# untitled.net
KiCad netlist of a schematic drawn in EAGLE
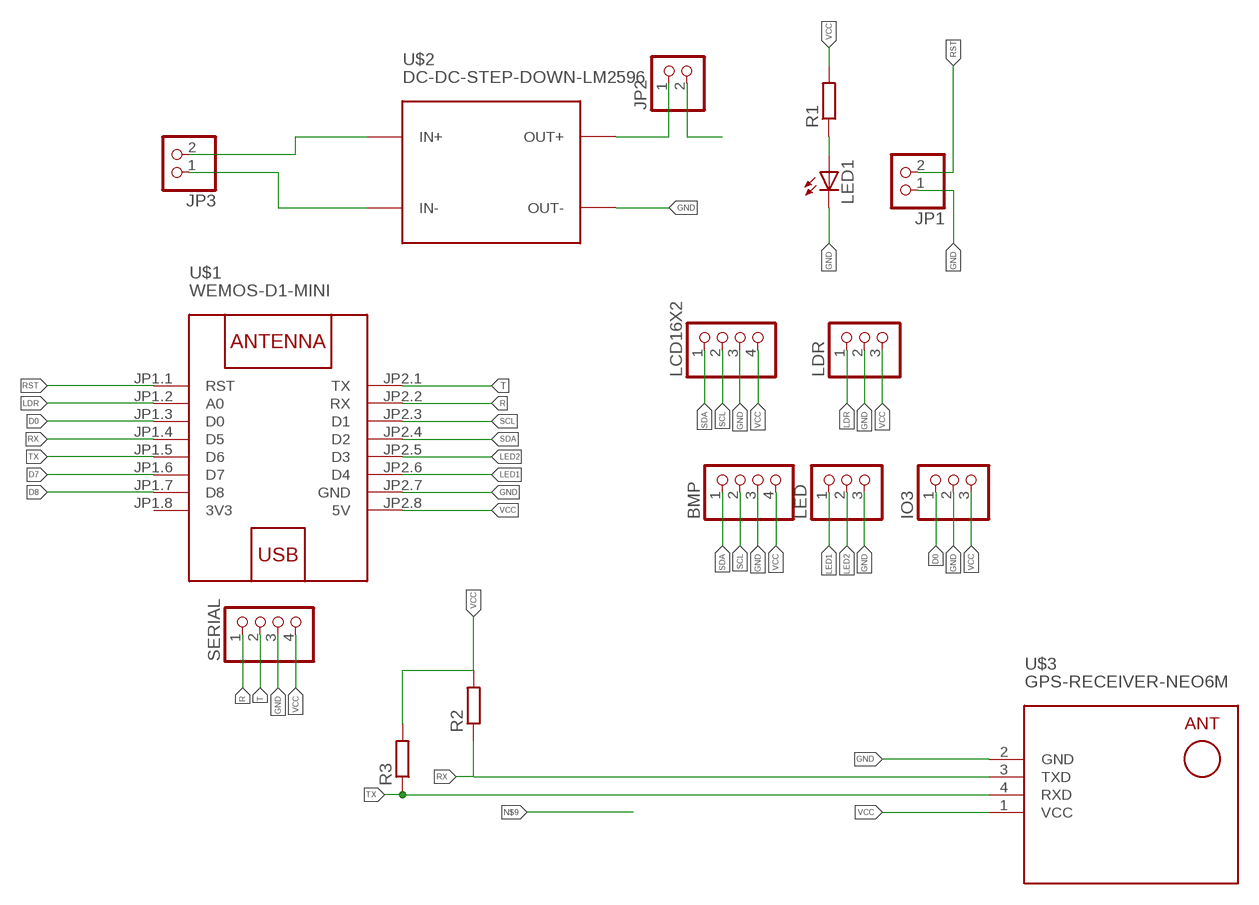
[diagram p0: schematic, sheet 1]

(export (version "E")
  (design (tool "Eeschema 10.0.6"))
  (components
    (comp (ref "BMP")
      (value "PINHD-1X4")
      (footprint "eagle-import:1X04")
      (libsource (lib "eagle-import") (part "PINHD-1X4"))
    )
    (comp (ref "IO3")
      (value "PINHD-1X3")
      (footprint "eagle-import:1X03")
      (libsource (lib "eagle-import") (part "PINHD-1X3"))
    )
    (comp (ref "JP1")
      (value "PINHD-1X2")
      (footprint "eagle-import:1X02")
      (libsource (lib "eagle-import") (part "PINHD-1X2"))
    )
    (comp (ref "JP2")
      (value "PINHD-1X2")
      (footprint "eagle-import:1X02")
      (libsource (lib "eagle-import") (part "PINHD-1X2"))
    )
    (comp (ref "JP3")
      (value "PINHD-1X2")
      (footprint "eagle-import:1X02")
      (libsource (lib "eagle-import") (part "PINHD-1X2"))
    )
    (comp (ref "LCD16X2")
      (value "PINHD-1X4")
      (footprint "eagle-import:1X04")
      (libsource (lib "eagle-import") (part "PINHD-1X4"))
    )
    (comp (ref "LDR")
      (value "PINHD-1X3")
      (footprint "eagle-import:1X03")
      (libsource (lib "eagle-import") (part "PINHD-1X3"))
    )
    (comp (ref "LED")
      (value "PINHD-1X3")
      (footprint "eagle-import:1X03")
      (libsource (lib "eagle-import") (part "PINHD-1X3"))
    )
    (comp (ref "LED1")
      (value "LED5MM")
      (footprint "eagle-import:LED5MM")
      (libsource (lib "eagle-import") (part "LED5MM"))
    )
    (comp (ref "R1")
      (value "R-EU_0204/7")
      (footprint "eagle-import:0204_7")
      (libsource (lib "eagle-import") (part "R-EU_0204/7"))
    )
    (comp (ref "R2")
      (value "R-EU_0204/7")
      (footprint "eagle-import:0204_7")
      (libsource (lib "eagle-import") (part "R-EU_0204/7"))
    )
    (comp (ref "R3")
      (value "R-EU_0204/7")
      (footprint "eagle-import:0204_7")
      (libsource (lib "eagle-import") (part "R-EU_0204/7"))
    )
    (comp (ref "SERIAL")
      (value "PINHD-1X4")
      (footprint "eagle-import:1X04")
      (libsource (lib "eagle-import") (part "PINHD-1X4"))
    )
    (comp (ref "U$1")
      (value "WEMOS-D1-MINI")
      (footprint "eagle-import:WEMOS-D1-MINI")
      (libsource (lib "eagle-import") (part "WEMOS-D1-MINI"))
    )
    (comp (ref "U$2")
      (value "DC-DC-STEP-DOWN-LM2596")
      (footprint "eagle-import:DC-DC-STEP-DOWN-LM2596")
      (libsource (lib "eagle-import") (part "DC-DC-STEP-DOWN-LM2596"))
    )
    (comp (ref "U$3")
      (value "GPS-RECEIVER-NEO6M")
      (footprint "eagle-import:GPS-RECEIVER-NEO6M")
      (libsource (lib "eagle-import") (part "GPS-RECEIVER-NEO6M"))
    )
  )
  (nets
    (net (code "1") (name "/3V3") (class "Default")
      (node (ref "U$1") (pin "JP1.8") (pinfunction "3V3_JP1.8") (pintype "power_in"))
    )
    (net (code "2") (name "D0") (class "Default")
      (node (ref "IO3") (pin "1") (pinfunction "1_1") (pintype "passive"))
      (node (ref "U$1") (pin "JP1.3") (pinfunction "D0_JP1.3") (pintype "bidirectional"))
    )
    (net (code "3") (name "D7") (class "Default")
      (node (ref "U$1") (pin "JP1.6") (pinfunction "D7_JP1.6") (pintype "bidirectional"))
    )
    (net (code "4") (name "D8") (class "Default")
      (node (ref "U$1") (pin "JP1.7") (pinfunction "D8_JP1.7") (pintype "bidirectional"))
    )
    (net (code "5") (name "GND") (class "Default")
      (node (ref "BMP") (pin "3") (pinfunction "3_3") (pintype "passive"))
      (node (ref "IO3") (pin "2") (pinfunction "2_2") (pintype "passive"))
      (node (ref "JP1") (pin "1") (pinfunction "1_1") (pintype "passive"))
      (node (ref "LCD16X2") (pin "3") (pinfunction "3_3") (pintype "passive"))
      (node (ref "LDR") (pin "2") (pinfunction "2_2") (pintype "passive"))
      (node (ref "LED") (pin "3") (pinfunction "3_3") (pintype "passive"))
      (node (ref "LED1") (pin "K") (pinfunction "C_K") (pintype "passive"))
      (node (ref "SERIAL") (pin "3") (pinfunction "3_3") (pintype "passive"))
      (node (ref "U$1") (pin "JP2.7") (pinfunction "GND_JP2.7") (pintype "power_in"))
      (node (ref "U$2") (pin "OUT-") (pinfunction "OUT-_OUT-") (pintype "bidirectional"))
      (node (ref "U$3") (pin "2") (pinfunction "GND_2") (pintype "bidirectional"))
    )
    (net (code "6") (name "LDR") (class "Default")
      (node (ref "LDR") (pin "1") (pinfunction "1_1") (pintype "passive"))
      (node (ref "U$1") (pin "JP1.2") (pinfunction "A0_JP1.2") (pintype "bidirectional"))
    )
    (net (code "7") (name "LED1") (class "Default")
      (node (ref "LED") (pin "1") (pinfunction "1_1") (pintype "passive"))
      (node (ref "U$1") (pin "JP2.6") (pinfunction "D4_JP2.6") (pintype "bidirectional"))
    )
    (net (code "8") (name "LED2") (class "Default")
      (node (ref "LED") (pin "2") (pinfunction "2_2") (pintype "passive"))
      (node (ref "U$1") (pin "JP2.5") (pinfunction "D3_JP2.5") (pintype "bidirectional"))
    )
    (net (code "10") (name "Net-(JP2-Pad1)") (class "Default")
      (node (ref "JP2") (pin "1") (pinfunction "1_1") (pintype "passive"))
      (node (ref "U$2") (pin "OUT+") (pinfunction "OUT+_OUT+") (pintype "bidirectional"))
    )
    (net (code "11") (name "Net-(JP3-Pad1)") (class "Default")
      (node (ref "JP3") (pin "1") (pinfunction "1_1") (pintype "passive"))
      (node (ref "U$2") (pin "IN-") (pinfunction "IN-_IN-") (pintype "bidirectional"))
    )
    (net (code "12") (name "Net-(JP3-Pad2)") (class "Default")
      (node (ref "JP3") (pin "2") (pinfunction "2_2") (pintype "passive"))
      (node (ref "U$2") (pin "IN+") (pinfunction "IN+_IN+") (pintype "bidirectional"))
    )
    (net (code "13") (name "Net-(LED1-PadA)") (class "Default")
      (node (ref "LED1") (pin "A") (pinfunction "A_A") (pintype "passive"))
      (node (ref "R1") (pin "1") (pinfunction "1_1") (pintype "passive"))
    )
    (net (code "14") (name "R") (class "Default")
      (node (ref "SERIAL") (pin "1") (pinfunction "1_1") (pintype "passive"))
      (node (ref "U$1") (pin "JP2.2") (pinfunction "RX_JP2.2") (pintype "bidirectional"))
    )
    (net (code "15") (name "RST") (class "Default")
      (node (ref "JP1") (pin "2") (pinfunction "2_2") (pintype "passive"))
      (node (ref "U$1") (pin "JP1.1") (pinfunction "RST_JP1.1") (pintype "bidirectional"))
    )
    (net (code "16") (name "RX") (class "Default")
      (node (ref "R2") (pin "1") (pinfunction "1_1") (pintype "passive"))
      (node (ref "U$1") (pin "JP1.4") (pinfunction "D5_JP1.4") (pintype "bidirectional"))
      (node (ref "U$3") (pin "3") (pinfunction "TXD_3") (pintype "bidirectional"))
    )
    (net (code "17") (name "SCL") (class "Default")
      (node (ref "BMP") (pin "2") (pinfunction "2_2") (pintype "passive"))
      (node (ref "LCD16X2") (pin "2") (pinfunction "2_2") (pintype "passive"))
      (node (ref "U$1") (pin "JP2.3") (pinfunction "D1_JP2.3") (pintype "bidirectional"))
    )
    (net (code "18") (name "SDA") (class "Default")
      (node (ref "BMP") (pin "1") (pinfunction "1_1") (pintype "passive"))
      (node (ref "LCD16X2") (pin "1") (pinfunction "1_1") (pintype "passive"))
      (node (ref "U$1") (pin "JP2.4") (pinfunction "D2_JP2.4") (pintype "bidirectional"))
    )
    (net (code "19") (name "T") (class "Default")
      (node (ref "SERIAL") (pin "2") (pinfunction "2_2") (pintype "passive"))
      (node (ref "U$1") (pin "JP2.1") (pinfunction "TX_JP2.1") (pintype "bidirectional"))
    )
    (net (code "20") (name "TX") (class "Default")
      (node (ref "R3") (pin "1") (pinfunction "1_1") (pintype "passive"))
      (node (ref "U$1") (pin "JP1.5") (pinfunction "D6_JP1.5") (pintype "bidirectional"))
      (node (ref "U$3") (pin "4") (pinfunction "RXD_4") (pintype "power_in"))
    )
    (net (code "21") (name "VCC") (class "Default")
      (node (ref "BMP") (pin "4") (pinfunction "4_4") (pintype "passive"))
      (node (ref "IO3") (pin "3") (pinfunction "3_3") (pintype "passive"))
      (node (ref "JP2") (pin "2") (pinfunction "2_2") (pintype "passive"))
      (node (ref "LCD16X2") (pin "4") (pinfunction "4_4") (pintype "passive"))
      (node (ref "LDR") (pin "3") (pinfunction "3_3") (pintype "passive"))
      (node (ref "R1") (pin "2") (pinfunction "2_2") (pintype "passive"))
      (node (ref "R2") (pin "2") (pinfunction "2_2") (pintype "passive"))
      (node (ref "R3") (pin "2") (pinfunction "2_2") (pintype "passive"))
      (node (ref "SERIAL") (pin "4") (pinfunction "4_4") (pintype "passive"))
      (node (ref "U$1") (pin "JP2.8") (pinfunction "5V_JP2.8") (pintype "power_in"))
      (node (ref "U$3") (pin "1") (pinfunction "VCC_1") (pintype "bidirectional"))
    )
  )
)
